# Simon-2021-Giveaway.net
KiCad netlist of a schematic drawn in EAGLE
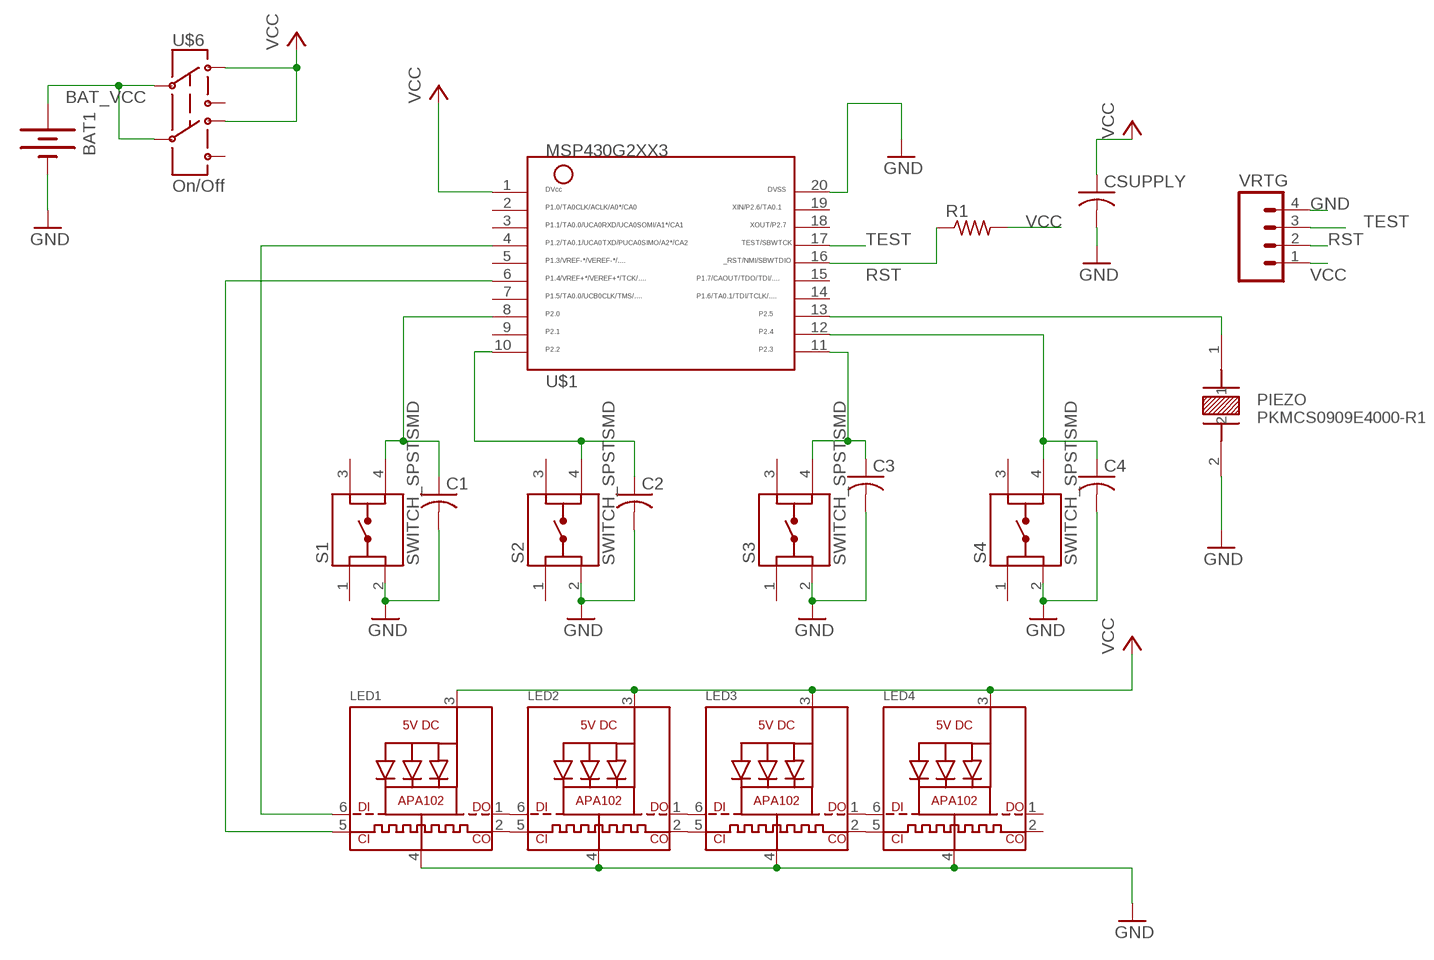
[diagram p0: schematic, sheet 1]

(export (version "E")
  (design (tool "Eeschema 10.0.6"))
  (components
    (comp (ref "BAT1")
      (value "BATTERY")
      (footprint "eagle-import:BATTERY_PACK_2AA")
      (libsource (lib "eagle-import") (part "BATTERY"))
    )
    (comp (ref "C1")
      (value "C-USC1206")
      (footprint "eagle-import:C1206")
      (libsource (lib "eagle-import") (part "C-USC1206"))
    )
    (comp (ref "C2")
      (value "C-USC1206")
      (footprint "eagle-import:C1206")
      (libsource (lib "eagle-import") (part "C-USC1206"))
    )
    (comp (ref "C3")
      (value "C-USC1206")
      (footprint "eagle-import:C1206")
      (libsource (lib "eagle-import") (part "C-USC1206"))
    )
    (comp (ref "C4")
      (value "C-USC1206")
      (footprint "eagle-import:C1206")
      (libsource (lib "eagle-import") (part "C-USC1206"))
    )
    (comp (ref "CSUPPLY")
      (value "C-USC1206")
      (footprint "eagle-import:C1206")
      (libsource (lib "eagle-import") (part "C-USC1206"))
    )
    (comp (ref "LED1")
      (value "APA1022020")
      (footprint "eagle-import:APA102_2020")
      (libsource (lib "eagle-import") (part "APA1022020"))
    )
    (comp (ref "LED2")
      (value "APA1022020")
      (footprint "eagle-import:APA102_2020")
      (libsource (lib "eagle-import") (part "APA1022020"))
    )
    (comp (ref "LED3")
      (value "APA1022020")
      (footprint "eagle-import:APA102_2020")
      (libsource (lib "eagle-import") (part "APA1022020"))
    )
    (comp (ref "LED4")
      (value "APA1022020")
      (footprint "eagle-import:APA102_2020")
      (libsource (lib "eagle-import") (part "APA1022020"))
    )
    (comp (ref "PIEZO")
      (value "PKMCS0909E4000-R1")
      (footprint "eagle-import:XDCR_PKMCS0909E4000-R1")
      (fields (field (name "DIGI-KEY_PART_NUMBER") "490-9647-1-ND") (field (name "MF") "Murata"))
      (libsource (lib "eagle-import") (part "PKMCS0909E4000-R1"))
    )
    (comp (ref "R1")
      (value "R-US_R1206")
      (footprint "eagle-import:R1206")
      (libsource (lib "eagle-import") (part "R-US_R1206"))
    )
    (comp (ref "S1")
      (value "SWITCH_SPSTSMD")
      (footprint "eagle-import:SW_1571563-4")
      (libsource (lib "eagle-import") (part "SWITCH_SPSTSMD"))
    )
    (comp (ref "S2")
      (value "SWITCH_SPSTSMD")
      (footprint "eagle-import:SW_1571563-4")
      (libsource (lib "eagle-import") (part "SWITCH_SPSTSMD"))
    )
    (comp (ref "S3")
      (value "SWITCH_SPSTSMD")
      (footprint "eagle-import:SW_1571563-4")
      (libsource (lib "eagle-import") (part "SWITCH_SPSTSMD"))
    )
    (comp (ref "S4")
      (value "SWITCH_SPSTSMD")
      (footprint "eagle-import:SW_1571563-4")
      (libsource (lib "eagle-import") (part "SWITCH_SPSTSMD"))
    )
    (comp (ref "U$1")
      (value "MSP430G2XX3TSSOP")
      (footprint "eagle-import:PW20")
      (libsource (lib "eagle-import") (part "MSP430G2XX3TSSOP"))
    )
    (comp (ref "U$6")
      (value "On/Off")
      (footprint "eagle-import:JS_DPDT_TH")
      (libsource (lib "eagle-import") (part "SWITCH_DPDT"))
    )
    (comp (ref "VRTG")
      (value "M04LOCK")
      (footprint "eagle-import:1X04_LOCK")
      (libsource (lib "eagle-import") (part "M04LOCK"))
    )
  )
  (nets
    (net (code "1") (name "/BAT_VCC") (class "Default")
      (node (ref "BAT1") (pin "3V") (pinfunction "+_3V") (pintype "power_in"))
      (node (ref "U$6") (pin "2") (pinfunction "2_2") (pintype "bidirectional"))
      (node (ref "U$6") (pin "5") (pinfunction "5_5") (pintype "bidirectional"))
    )
    (net (code "2") (name "/RST") (class "Default")
      (node (ref "R1") (pin "1") (pinfunction "1_1") (pintype "passive"))
      (node (ref "U$1") (pin "16") (pinfunction "16_16") (pintype "bidirectional"))
      (node (ref "VRTG") (pin "2") (pinfunction "2_2") (pintype "passive"))
    )
    (net (code "3") (name "/TEST") (class "Default")
      (node (ref "U$1") (pin "17") (pinfunction "17_17") (pintype "bidirectional"))
      (node (ref "VRTG") (pin "3") (pinfunction "3_3") (pintype "passive"))
    )
    (net (code "4") (name "GND") (class "Default")
      (node (ref "BAT1") (pin "GND") (pinfunction "-_GND") (pintype "power_in"))
      (node (ref "C1") (pin "2") (pinfunction "2_2") (pintype "passive"))
      (node (ref "C2") (pin "2") (pinfunction "2_2") (pintype "passive"))
      (node (ref "C3") (pin "2") (pinfunction "2_2") (pintype "passive"))
      (node (ref "C4") (pin "2") (pinfunction "2_2") (pintype "passive"))
      (node (ref "CSUPPLY") (pin "2") (pinfunction "2_2") (pintype "passive"))
      (node (ref "LED1") (pin "4") (pinfunction "GND_4") (pintype "power_in"))
      (node (ref "LED2") (pin "4") (pinfunction "GND_4") (pintype "power_in"))
      (node (ref "LED3") (pin "4") (pinfunction "GND_4") (pintype "power_in"))
      (node (ref "LED4") (pin "4") (pinfunction "GND_4") (pintype "power_in"))
      (node (ref "PIEZO") (pin "2") (pinfunction "2_2") (pintype "passive"))
      (node (ref "S1") (pin "2") (pinfunction "2_2") (pintype "passive"))
      (node (ref "S2") (pin "2") (pinfunction "2_2") (pintype "passive"))
      (node (ref "S3") (pin "2") (pinfunction "2_2") (pintype "passive"))
      (node (ref "S4") (pin "2") (pinfunction "2_2") (pintype "passive"))
      (node (ref "U$1") (pin "20") (pinfunction "20_20") (pintype "bidirectional"))
      (node (ref "VRTG") (pin "4") (pinfunction "4_4") (pintype "passive"))
    )
    (net (code "5") (name "Net-(C1-Pad1)") (class "Default")
      (node (ref "C1") (pin "1") (pinfunction "1_1") (pintype "passive"))
      (node (ref "S1") (pin "4") (pinfunction "4_4") (pintype "passive"))
      (node (ref "U$1") (pin "8") (pinfunction "8_8") (pintype "bidirectional"))
    )
    (net (code "6") (name "Net-(C2-Pad1)") (class "Default")
      (node (ref "C2") (pin "1") (pinfunction "1_1") (pintype "passive"))
      (node (ref "S2") (pin "4") (pinfunction "4_4") (pintype "passive"))
      (node (ref "U$1") (pin "10") (pinfunction "10_10") (pintype "bidirectional"))
    )
    (net (code "7") (name "Net-(C3-Pad1)") (class "Default")
      (node (ref "C3") (pin "1") (pinfunction "1_1") (pintype "passive"))
      (node (ref "S3") (pin "4") (pinfunction "4_4") (pintype "passive"))
      (node (ref "U$1") (pin "11") (pinfunction "11_11") (pintype "bidirectional"))
    )
    (net (code "8") (name "Net-(C4-Pad1)") (class "Default")
      (node (ref "C4") (pin "1") (pinfunction "1_1") (pintype "passive"))
      (node (ref "S4") (pin "4") (pinfunction "4_4") (pintype "passive"))
      (node (ref "U$1") (pin "12") (pinfunction "12_12") (pintype "bidirectional"))
    )
    (net (code "9") (name "Net-(LED1-CKI)") (class "Default")
      (node (ref "LED1") (pin "5") (pinfunction "CKI_5") (pintype "input"))
      (node (ref "U$1") (pin "6") (pinfunction "6_6") (pintype "bidirectional"))
    )
    (net (code "10") (name "Net-(LED1-CKO)") (class "Default")
      (node (ref "LED1") (pin "2") (pinfunction "CKO_2") (pintype "output"))
      (node (ref "LED2") (pin "5") (pinfunction "CKI_5") (pintype "input"))
    )
    (net (code "11") (name "Net-(LED1-DI)") (class "Default")
      (node (ref "LED1") (pin "6") (pinfunction "DI_6") (pintype "input"))
      (node (ref "U$1") (pin "4") (pinfunction "4_4") (pintype "bidirectional"))
    )
    (net (code "12") (name "Net-(LED1-DO)") (class "Default")
      (node (ref "LED1") (pin "1") (pinfunction "DO_1") (pintype "output"))
      (node (ref "LED2") (pin "6") (pinfunction "DI_6") (pintype "input"))
    )
    (net (code "13") (name "Net-(LED2-CKO)") (class "Default")
      (node (ref "LED2") (pin "2") (pinfunction "CKO_2") (pintype "output"))
      (node (ref "LED3") (pin "5") (pinfunction "CKI_5") (pintype "input"))
    )
    (net (code "14") (name "Net-(LED2-DO)") (class "Default")
      (node (ref "LED2") (pin "1") (pinfunction "DO_1") (pintype "output"))
      (node (ref "LED3") (pin "6") (pinfunction "DI_6") (pintype "input"))
    )
    (net (code "15") (name "Net-(LED3-CKO)") (class "Default")
      (node (ref "LED3") (pin "2") (pinfunction "CKO_2") (pintype "output"))
      (node (ref "LED4") (pin "5") (pinfunction "CKI_5") (pintype "input"))
    )
    (net (code "16") (name "Net-(LED3-DO)") (class "Default")
      (node (ref "LED3") (pin "1") (pinfunction "DO_1") (pintype "output"))
      (node (ref "LED4") (pin "6") (pinfunction "DI_6") (pintype "input"))
    )
    (net (code "17") (name "Net-(PIEZO-Pad1)") (class "Default")
      (node (ref "PIEZO") (pin "1") (pinfunction "1_1") (pintype "passive"))
      (node (ref "U$1") (pin "13") (pinfunction "13_13") (pintype "bidirectional"))
    )
    (net (code "18") (name "VCC") (class "Default")
      (node (ref "CSUPPLY") (pin "1") (pinfunction "1_1") (pintype "passive"))
      (node (ref "LED1") (pin "3") (pinfunction "VDD_3") (pintype "power_in"))
      (node (ref "LED2") (pin "3") (pinfunction "VDD_3") (pintype "power_in"))
      (node (ref "LED3") (pin "3") (pinfunction "VDD_3") (pintype "power_in"))
      (node (ref "LED4") (pin "3") (pinfunction "VDD_3") (pintype "power_in"))
      (node (ref "R1") (pin "2") (pinfunction "2_2") (pintype "passive"))
      (node (ref "U$1") (pin "1") (pinfunction "1_1") (pintype "bidirectional"))
      (node (ref "U$6") (pin "1") (pinfunction "1_1") (pintype "bidirectional"))
      (node (ref "U$6") (pin "4") (pinfunction "4_4") (pintype "bidirectional"))
      (node (ref "VRTG") (pin "1") (pinfunction "1_1") (pintype "passive"))
    )
    (net (code "19") (name "unconnected-(LED4-CKO-Pad2)") (class "Default")
      (node (ref "LED4") (pin "2") (pinfunction "CKO_2") (pintype "output"))
    )
    (net (code "20") (name "unconnected-(LED4-DO-Pad1)") (class "Default")
      (node (ref "LED4") (pin "1") (pinfunction "DO_1") (pintype "output"))
    )
    (net (code "21") (name "unconnected-(S1-Pad1)") (class "Default")
      (node (ref "S1") (pin "1") (pinfunction "1_1") (pintype "passive"))
    )
    (net (code "22") (name "unconnected-(S1-Pad3)") (class "Default")
      (node (ref "S1") (pin "3") (pinfunction "3_3") (pintype "passive"))
    )
    (net (code "23") (name "unconnected-(S2-Pad1)") (class "Default")
      (node (ref "S2") (pin "1") (pinfunction "1_1") (pintype "passive"))
    )
    (net (code "24") (name "unconnected-(S2-Pad3)") (class "Default")
      (node (ref "S2") (pin "3") (pinfunction "3_3") (pintype "passive"))
    )
    (net (code "25") (name "unconnected-(S3-Pad1)") (class "Default")
      (node (ref "S3") (pin "1") (pinfunction "1_1") (pintype "passive"))
    )
    (net (code "26") (name "unconnected-(S3-Pad3)") (class "Default")
      (node (ref "S3") (pin "3") (pinfunction "3_3") (pintype "passive"))
    )
    (net (code "27") (name "unconnected-(S4-Pad1)") (class "Default")
      (node (ref "S4") (pin "1") (pinfunction "1_1") (pintype "passive"))
    )
    (net (code "28") (name "unconnected-(S4-Pad3)") (class "Default")
      (node (ref "S4") (pin "3") (pinfunction "3_3") (pintype "passive"))
    )
    (net (code "29") (name "unconnected-(U$1-Pad2)") (class "Default")
      (node (ref "U$1") (pin "2") (pinfunction "2_2") (pintype "bidirectional"))
    )
    (net (code "30") (name "unconnected-(U$1-Pad3)") (class "Default")
      (node (ref "U$1") (pin "3") (pinfunction "3_3") (pintype "bidirectional"))
    )
    (net (code "31") (name "unconnected-(U$1-Pad5)") (class "Default")
      (node (ref "U$1") (pin "5") (pinfunction "5_5") (pintype "bidirectional"))
    )
    (net (code "32") (name "unconnected-(U$1-Pad7)") (class "Default")
      (node (ref "U$1") (pin "7") (pinfunction "7_7") (pintype "bidirectional"))
    )
    (net (code "33") (name "unconnected-(U$1-Pad9)") (class "Default")
      (node (ref "U$1") (pin "9") (pinfunction "9_9") (pintype "bidirectional"))
    )
    (net (code "34") (name "unconnected-(U$1-Pad14)") (class "Default")
      (node (ref "U$1") (pin "14") (pinfunction "14_14") (pintype "bidirectional"))
    )
    (net (code "35") (name "unconnected-(U$1-Pad15)") (class "Default")
      (node (ref "U$1") (pin "15") (pinfunction "15_15") (pintype "bidirectional"))
    )
    (net (code "36") (name "unconnected-(U$1-Pad18)") (class "Default")
      (node (ref "U$1") (pin "18") (pinfunction "18_18") (pintype "bidirectional"))
    )
    (net (code "37") (name "unconnected-(U$1-Pad19)") (class "Default")
      (node (ref "U$1") (pin "19") (pinfunction "19_19") (pintype "bidirectional"))
    )
    (net (code "38") (name "unconnected-(U$6-Pad3)") (class "Default")
      (node (ref "U$6") (pin "3") (pinfunction "3_3") (pintype "bidirectional"))
    )
    (net (code "39") (name "unconnected-(U$6-Pad6)") (class "Default")
      (node (ref "U$6") (pin "6") (pinfunction "6_6") (pintype "bidirectional"))
    )
  )
)
